# smt.net
KiCad netlist of a schematic drawn in EAGLE
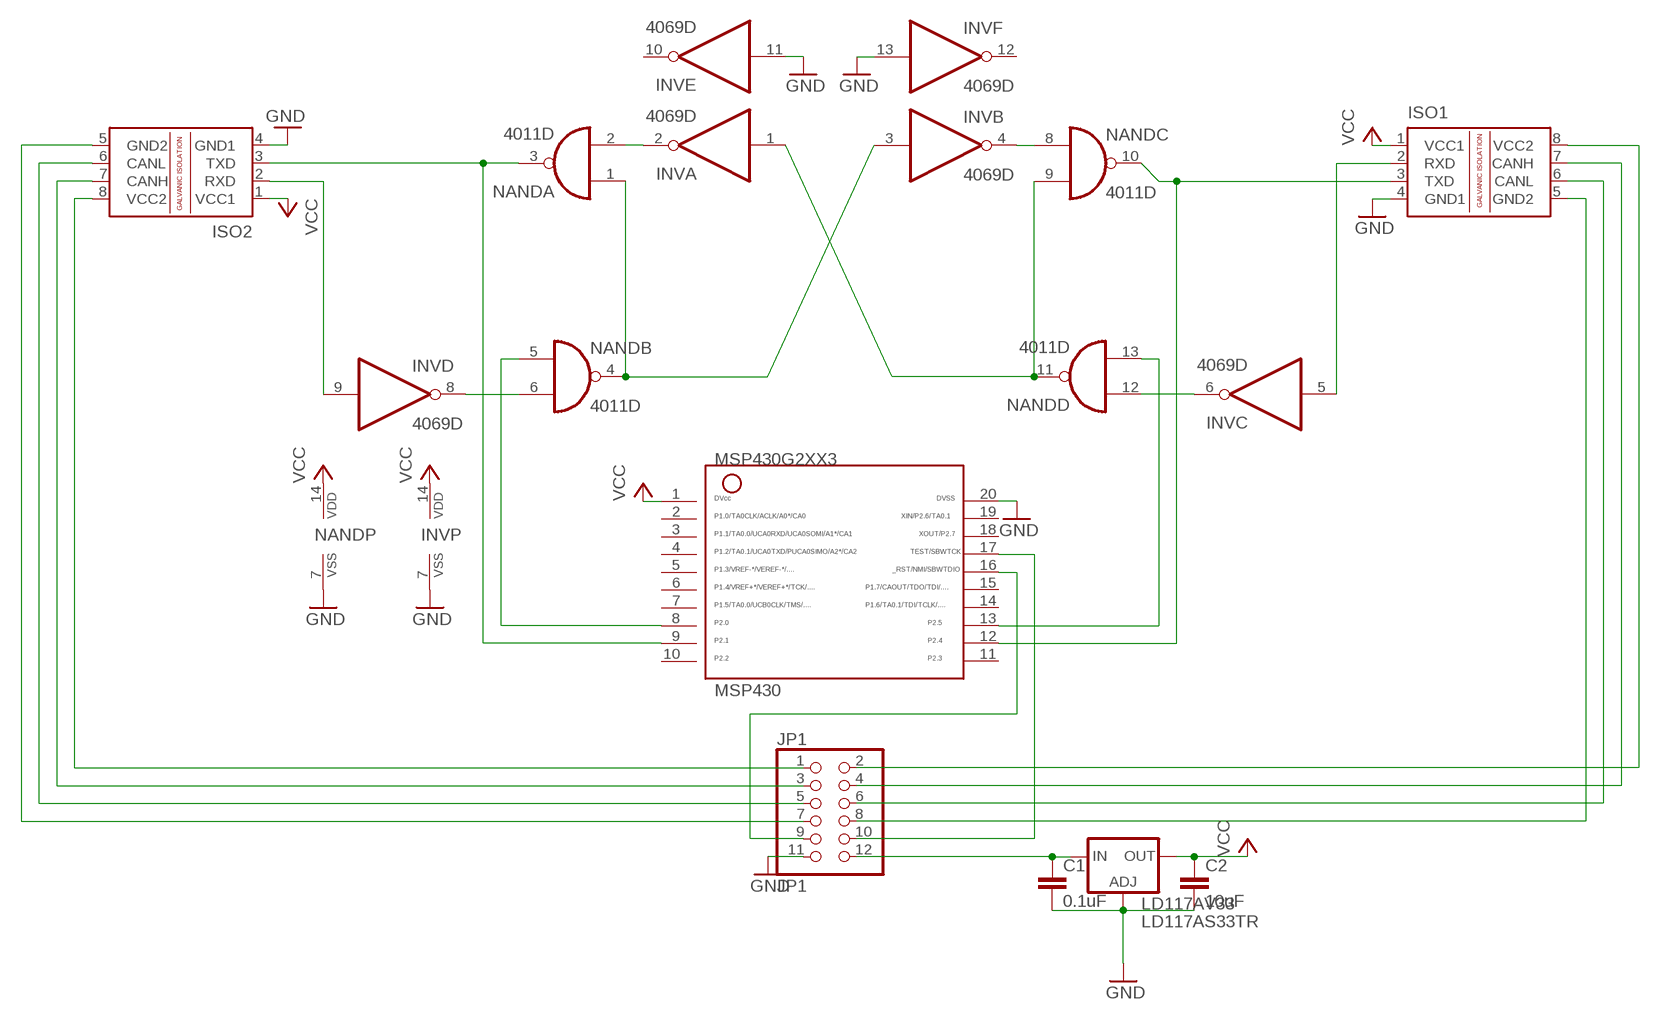
[diagram p0: schematic, sheet 1]

(export (version "E")
  (design (tool "Eeschema 10.0.6"))
  (components
    (comp (ref "C1")
      (value "0.1uF")
      (footprint "eagle-import:C0402")
      (libsource (lib "eagle-import") (part "C-EUC0402"))
    )
    (comp (ref "C2")
      (value "10uF")
      (footprint "eagle-import:C0402")
      (libsource (lib "eagle-import") (part "C-EUC0402"))
    )
    (comp (ref "INV")
      (value "4069D")
      (footprint "eagle-import:SO14")
      (libsource (lib "eagle-import") (part "4069D"))
    )
    (comp (ref "ISO1")
      (value "ISO1050DUB")
      (footprint "eagle-import:DUB-R-PDSO-G8")
      (fields (field (name "MPN") "ISO1050DUBR"))
      (libsource (lib "eagle-import") (part "ISO1050DUB"))
    )
    (comp (ref "ISO2")
      (value "ISO1050DUB")
      (footprint "eagle-import:DUB-R-PDSO-G8")
      (fields (field (name "MPN") "ISO1050DUBR"))
      (libsource (lib "eagle-import") (part "ISO1050DUB"))
    )
    (comp (ref "JP1")
      (value "JP1")
      (footprint "eagle-import:2X06")
      (libsource (lib "eagle-import") (part "PINHD-2X6"))
    )
    (comp (ref "LD117AV33")
      (value "LD117AS33TR")
      (footprint "eagle-import:SOT223")
      (libsource (lib "eagle-import") (part "LD117A?S33TR"))
    )
    (comp (ref "MSP430")
      (value "G2XX3---PW20")
      (footprint "eagle-import:PW20")
      (libsource (lib "eagle-import") (part "G2XX3---PW20"))
    )
    (comp (ref "NAND")
      (value "4011D")
      (footprint "eagle-import:SO14")
      (libsource (lib "eagle-import") (part "4011D"))
    )
  )
  (nets
    (net (code "1") (name "GND") (class "Default")
      (node (ref "C1") (pin "2") (pinfunction "2_2") (pintype "passive"))
      (node (ref "C2") (pin "2") (pinfunction "2_2") (pintype "passive"))
      (node (ref "INV") (pin "11") (pinfunction "I_11") (pintype "input"))
      (node (ref "INV") (pin "13") (pinfunction "I_13") (pintype "input"))
      (node (ref "INV") (pin "7") (pinfunction "VSS_7") (pintype "power_in"))
      (node (ref "ISO1") (pin "4") (pinfunction "GND1_4") (pintype "input"))
      (node (ref "ISO2") (pin "4") (pinfunction "GND1_4") (pintype "input"))
      (node (ref "JP1") (pin "11") (pinfunction "11_11") (pintype "passive"))
      (node (ref "LD117AV33") (pin "1") (pinfunction "ADJ_1") (pintype "input"))
      (node (ref "MSP430") (pin "20") (pinfunction "20_20") (pintype "bidirectional"))
      (node (ref "NAND") (pin "7") (pinfunction "VSS_7") (pintype "power_in"))
    )
    (net (code "2") (name "Net-(INVA-I)") (class "Default")
      (node (ref "INV") (pin "1") (pinfunction "I_1") (pintype "input"))
      (node (ref "NAND") (pin "11") (pinfunction "O_11") (pintype "output"))
      (node (ref "NAND") (pin "9") (pinfunction "I1_9") (pintype "input"))
    )
    (net (code "3") (name "Net-(INVA-O)") (class "Default")
      (node (ref "INV") (pin "2") (pinfunction "O_2") (pintype "output"))
      (node (ref "NAND") (pin "2") (pinfunction "I1_2") (pintype "input"))
    )
    (net (code "4") (name "Net-(INVB-I)") (class "Default")
      (node (ref "INV") (pin "3") (pinfunction "I_3") (pintype "input"))
      (node (ref "NAND") (pin "1") (pinfunction "I0_1") (pintype "input"))
      (node (ref "NAND") (pin "4") (pinfunction "O_4") (pintype "output"))
    )
    (net (code "5") (name "Net-(INVB-O)") (class "Default")
      (node (ref "INV") (pin "4") (pinfunction "O_4") (pintype "output"))
      (node (ref "NAND") (pin "8") (pinfunction "I0_8") (pintype "input"))
    )
    (net (code "6") (name "Net-(INVC-I)") (class "Default")
      (node (ref "INV") (pin "5") (pinfunction "I_5") (pintype "input"))
      (node (ref "ISO1") (pin "2") (pinfunction "RXD_2") (pintype "input"))
    )
    (net (code "7") (name "Net-(INVC-O)") (class "Default")
      (node (ref "INV") (pin "6") (pinfunction "O_6") (pintype "output"))
      (node (ref "NAND") (pin "12") (pinfunction "I0_12") (pintype "input"))
    )
    (net (code "8") (name "Net-(INVD-I)") (class "Default")
      (node (ref "INV") (pin "9") (pinfunction "I_9") (pintype "input"))
      (node (ref "ISO2") (pin "2") (pinfunction "RXD_2") (pintype "input"))
    )
    (net (code "9") (name "Net-(INVD-O)") (class "Default")
      (node (ref "INV") (pin "8") (pinfunction "O_8") (pintype "output"))
      (node (ref "NAND") (pin "6") (pinfunction "I1_6") (pintype "input"))
    )
    (net (code "10") (name "Net-(ISO1-CANH)") (class "Default")
      (node (ref "ISO1") (pin "7") (pinfunction "CANH_7") (pintype "input"))
      (node (ref "JP1") (pin "4") (pinfunction "4_4") (pintype "passive"))
    )
    (net (code "11") (name "Net-(ISO1-CANL)") (class "Default")
      (node (ref "ISO1") (pin "6") (pinfunction "CANL_6") (pintype "input"))
      (node (ref "JP1") (pin "6") (pinfunction "6_6") (pintype "passive"))
    )
    (net (code "12") (name "Net-(ISO1-GND2)") (class "Default")
      (node (ref "ISO1") (pin "5") (pinfunction "GND2_5") (pintype "input"))
      (node (ref "JP1") (pin "8") (pinfunction "8_8") (pintype "passive"))
    )
    (net (code "13") (name "Net-(ISO1-TXD)") (class "Default")
      (node (ref "ISO1") (pin "3") (pinfunction "TXD_3") (pintype "input"))
      (node (ref "MSP430") (pin "12") (pinfunction "12_12") (pintype "bidirectional"))
      (node (ref "NAND") (pin "10") (pinfunction "O_10") (pintype "output"))
    )
    (net (code "14") (name "Net-(ISO1-VCC2)") (class "Default")
      (node (ref "ISO1") (pin "8") (pinfunction "VCC2_8") (pintype "input"))
      (node (ref "JP1") (pin "2") (pinfunction "2_2") (pintype "passive"))
    )
    (net (code "15") (name "Net-(ISO2-CANH)") (class "Default")
      (node (ref "ISO2") (pin "7") (pinfunction "CANH_7") (pintype "input"))
      (node (ref "JP1") (pin "3") (pinfunction "3_3") (pintype "passive"))
    )
    (net (code "16") (name "Net-(ISO2-CANL)") (class "Default")
      (node (ref "ISO2") (pin "6") (pinfunction "CANL_6") (pintype "input"))
      (node (ref "JP1") (pin "5") (pinfunction "5_5") (pintype "passive"))
    )
    (net (code "17") (name "Net-(ISO2-GND2)") (class "Default")
      (node (ref "ISO2") (pin "5") (pinfunction "GND2_5") (pintype "input"))
      (node (ref "JP1") (pin "7") (pinfunction "7_7") (pintype "passive"))
    )
    (net (code "18") (name "Net-(ISO2-TXD)") (class "Default")
      (node (ref "ISO2") (pin "3") (pinfunction "TXD_3") (pintype "input"))
      (node (ref "MSP430") (pin "9") (pinfunction "9_9") (pintype "bidirectional"))
      (node (ref "NAND") (pin "3") (pinfunction "O_3") (pintype "output"))
    )
    (net (code "19") (name "Net-(ISO2-VCC2)") (class "Default")
      (node (ref "ISO2") (pin "8") (pinfunction "VCC2_8") (pintype "input"))
      (node (ref "JP1") (pin "1") (pinfunction "1_1") (pintype "passive"))
    )
    (net (code "20") (name "Net-(JP1-Pad9)") (class "Default")
      (node (ref "JP1") (pin "9") (pinfunction "9_9") (pintype "passive"))
      (node (ref "MSP430") (pin "16") (pinfunction "16_16") (pintype "bidirectional"))
    )
    (net (code "21") (name "Net-(JP1-Pad10)") (class "Default")
      (node (ref "JP1") (pin "10") (pinfunction "10_10") (pintype "passive"))
      (node (ref "MSP430") (pin "17") (pinfunction "17_17") (pintype "bidirectional"))
    )
    (net (code "22") (name "Net-(LD117AV33-IN)") (class "Default")
      (node (ref "C1") (pin "1") (pinfunction "1_1") (pintype "passive"))
      (node (ref "JP1") (pin "12") (pinfunction "12_12") (pintype "passive"))
      (node (ref "LD117AV33") (pin "3") (pinfunction "IN_3") (pintype "input"))
    )
    (net (code "23") (name "Net-(NANDB-I0)") (class "Default")
      (node (ref "MSP430") (pin "8") (pinfunction "8_8") (pintype "bidirectional"))
      (node (ref "NAND") (pin "5") (pinfunction "I0_5") (pintype "input"))
    )
    (net (code "24") (name "Net-(NANDD-I1)") (class "Default")
      (node (ref "MSP430") (pin "13") (pinfunction "13_13") (pintype "bidirectional"))
      (node (ref "NAND") (pin "13") (pinfunction "I1_13") (pintype "input"))
    )
    (net (code "25") (name "VCC") (class "Default")
      (node (ref "C2") (pin "1") (pinfunction "1_1") (pintype "passive"))
      (node (ref "INV") (pin "14") (pinfunction "VDD_14") (pintype "power_in"))
      (node (ref "ISO1") (pin "1") (pinfunction "VCC1_1") (pintype "input"))
      (node (ref "ISO2") (pin "1") (pinfunction "VCC1_1") (pintype "input"))
      (node (ref "LD117AV33") (pin "4") (pinfunction "OUT_4") (pintype "passive"))
      (node (ref "MSP430") (pin "1") (pinfunction "1_1") (pintype "bidirectional"))
      (node (ref "NAND") (pin "14") (pinfunction "VDD_14") (pintype "power_in"))
    )
    (net (code "26") (name "unconnected-(INVE-O-Pad10)") (class "Default")
      (node (ref "INV") (pin "10") (pinfunction "O_10") (pintype "output"))
    )
    (net (code "27") (name "unconnected-(INVF-O-Pad12)") (class "Default")
      (node (ref "INV") (pin "12") (pinfunction "O_12") (pintype "output"))
    )
    (net (code "28") (name "unconnected-(MSP430-Pad2)") (class "Default")
      (node (ref "MSP430") (pin "2") (pinfunction "2_2") (pintype "bidirectional"))
    )
    (net (code "29") (name "unconnected-(MSP430-Pad3)") (class "Default")
      (node (ref "MSP430") (pin "3") (pinfunction "3_3") (pintype "bidirectional"))
    )
    (net (code "30") (name "unconnected-(MSP430-Pad4)") (class "Default")
      (node (ref "MSP430") (pin "4") (pinfunction "4_4") (pintype "bidirectional"))
    )
    (net (code "31") (name "unconnected-(MSP430-Pad5)") (class "Default")
      (node (ref "MSP430") (pin "5") (pinfunction "5_5") (pintype "bidirectional"))
    )
    (net (code "32") (name "unconnected-(MSP430-Pad6)") (class "Default")
      (node (ref "MSP430") (pin "6") (pinfunction "6_6") (pintype "bidirectional"))
    )
    (net (code "33") (name "unconnected-(MSP430-Pad7)") (class "Default")
      (node (ref "MSP430") (pin "7") (pinfunction "7_7") (pintype "bidirectional"))
    )
    (net (code "34") (name "unconnected-(MSP430-Pad10)") (class "Default")
      (node (ref "MSP430") (pin "10") (pinfunction "10_10") (pintype "bidirectional"))
    )
    (net (code "35") (name "unconnected-(MSP430-Pad11)") (class "Default")
      (node (ref "MSP430") (pin "11") (pinfunction "11_11") (pintype "bidirectional"))
    )
    (net (code "36") (name "unconnected-(MSP430-Pad14)") (class "Default")
      (node (ref "MSP430") (pin "14") (pinfunction "14_14") (pintype "bidirectional"))
    )
    (net (code "37") (name "unconnected-(MSP430-Pad15)") (class "Default")
      (node (ref "MSP430") (pin "15") (pinfunction "15_15") (pintype "bidirectional"))
    )
    (net (code "38") (name "unconnected-(MSP430-Pad18)") (class "Default")
      (node (ref "MSP430") (pin "18") (pinfunction "18_18") (pintype "bidirectional"))
    )
    (net (code "39") (name "unconnected-(MSP430-Pad19)") (class "Default")
      (node (ref "MSP430") (pin "19") (pinfunction "19_19") (pintype "bidirectional"))
    )
  )
)
